# board.net
KiCad netlist of a schematic drawn in EAGLE
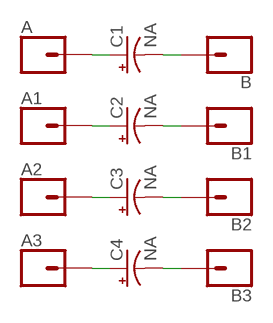
[diagram p0: schematic, sheet 1]

(export (version "E")
  (design (tool "Eeschema 10.0.6"))
  (components
    (comp (ref "A")
      (value "CONN_01")
      (footprint "eagle-import:1X01")
      (libsource (lib "eagle-import") (part "CONN_01"))
    )
    (comp (ref "A1")
      (value "CONN_01")
      (footprint "eagle-import:1X01")
      (libsource (lib "eagle-import") (part "CONN_01"))
    )
    (comp (ref "A2")
      (value "CONN_01")
      (footprint "eagle-import:1X01")
      (libsource (lib "eagle-import") (part "CONN_01"))
    )
    (comp (ref "A3")
      (value "CONN_01")
      (footprint "eagle-import:1X01")
      (libsource (lib "eagle-import") (part "CONN_01"))
    )
    (comp (ref "B")
      (value "CONN_01")
      (footprint "eagle-import:1X01")
      (libsource (lib "eagle-import") (part "CONN_01"))
    )
    (comp (ref "B1")
      (value "CONN_01")
      (footprint "eagle-import:1X01")
      (libsource (lib "eagle-import") (part "CONN_01"))
    )
    (comp (ref "B2")
      (value "CONN_01")
      (footprint "eagle-import:1X01")
      (libsource (lib "eagle-import") (part "CONN_01"))
    )
    (comp (ref "B3")
      (value "CONN_01")
      (footprint "eagle-import:1X01")
      (libsource (lib "eagle-import") (part "CONN_01"))
    )
    (comp (ref "C1")
      (value "NA")
      (footprint "eagle-import:CPOL-RADIAL-2.5MM-5MM")
      (libsource (lib "eagle-import") (part "10UF-POLAR-RADIAL-2.5MM-25V-20%"))
    )
    (comp (ref "C2")
      (value "NA")
      (footprint "eagle-import:CPOL-RADIAL-2.5MM-5MM")
      (libsource (lib "eagle-import") (part "10UF-POLAR-RADIAL-2.5MM-25V-20%"))
    )
    (comp (ref "C3")
      (value "NA")
      (footprint "eagle-import:CPOL-RADIAL-2.5MM-5MM")
      (libsource (lib "eagle-import") (part "10UF-POLAR-RADIAL-2.5MM-25V-20%"))
    )
    (comp (ref "C4")
      (value "NA")
      (footprint "eagle-import:CPOL-RADIAL-2.5MM-5MM")
      (libsource (lib "eagle-import") (part "10UF-POLAR-RADIAL-2.5MM-25V-20%"))
    )
  )
  (nets
    (net (code "1") (name "Net-(C1-+)") (class "Default")
      (node (ref "A") (pin "1") (pinfunction "1_1") (pintype "passive"))
      (node (ref "C1") (pin "1") (pinfunction "+_1") (pintype "passive"))
    )
    (net (code "2") (name "Net-(C1--)") (class "Default")
      (node (ref "B") (pin "1") (pinfunction "1_1") (pintype "passive"))
      (node (ref "C1") (pin "2") (pinfunction "-_2") (pintype "passive"))
    )
    (net (code "3") (name "Net-(C2-+)") (class "Default")
      (node (ref "A1") (pin "1") (pinfunction "1_1") (pintype "passive"))
      (node (ref "C2") (pin "1") (pinfunction "+_1") (pintype "passive"))
    )
    (net (code "4") (name "Net-(C2--)") (class "Default")
      (node (ref "B1") (pin "1") (pinfunction "1_1") (pintype "passive"))
      (node (ref "C2") (pin "2") (pinfunction "-_2") (pintype "passive"))
    )
    (net (code "5") (name "Net-(C3-+)") (class "Default")
      (node (ref "A2") (pin "1") (pinfunction "1_1") (pintype "passive"))
      (node (ref "C3") (pin "1") (pinfunction "+_1") (pintype "passive"))
    )
    (net (code "6") (name "Net-(C3--)") (class "Default")
      (node (ref "B2") (pin "1") (pinfunction "1_1") (pintype "passive"))
      (node (ref "C3") (pin "2") (pinfunction "-_2") (pintype "passive"))
    )
    (net (code "7") (name "Net-(C4-+)") (class "Default")
      (node (ref "A3") (pin "1") (pinfunction "1_1") (pintype "passive"))
      (node (ref "C4") (pin "1") (pinfunction "+_1") (pintype "passive"))
    )
    (net (code "8") (name "Net-(C4--)") (class "Default")
      (node (ref "B3") (pin "1") (pinfunction "1_1") (pintype "passive"))
      (node (ref "C4") (pin "2") (pinfunction "-_2") (pintype "passive"))
    )
  )
)
